# Perpherials.net
KiCad netlist of a schematic drawn in Altium Designer
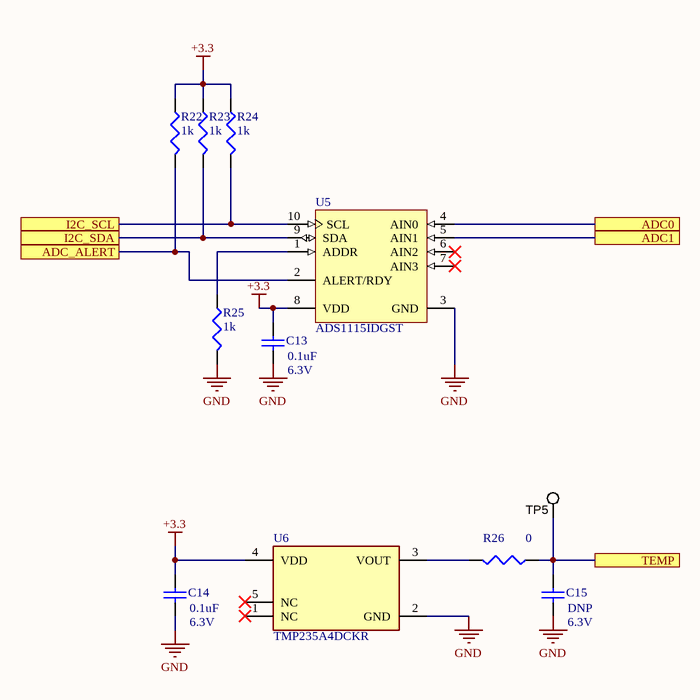
[diagram p0: Perpherials.SchDoc]

(export (version "E")
  (design (tool "Eeschema 10.0.6"))
  (components
    (comp (ref "C13")
      (value "0.1uF")
      (footprint "1608[0603]")
      (description "Capacitor (Semiconductor SIM Model)")
      (fields
        (field (name "VOLTAGE") "6.3V")
        (field (name "MPN") "06036C104KAT4A")
        (field (name "MANUFACTURER") "AVX Corporation")
        (field (name "PUBLISHER") "Altium Limited")
      )
      (libsource (lib "Miscellaneous Devices") (part "Cap Semi"))
    )
    (comp (ref "C14")
      (value "0.1uF")
      (footprint "1608[0603]")
      (description "Capacitor (Semiconductor SIM Model)")
      (fields
        (field (name "VOLTAGE") "6.3V")
        (field (name "MPN") "06036C104KAT4A")
        (field (name "MANUFACTURER") "AVX Corporation")
        (field (name "PUBLISHER") "Altium Limited")
      )
      (libsource (lib "Miscellaneous Devices") (part "Cap Semi"))
    )
    (comp (ref "C15")
      (value "DNP")
      (footprint "1608[0603]")
      (description "Capacitor (Semiconductor SIM Model)")
      (fields
        (field (name "VOLTAGE") "6.3V")
        (field (name "Comment") "Cap Semi")
        (field (name "PUBLISHER") "Altium Limited")
      )
      (libsource (lib "Miscellaneous Devices") (part "Cap Semi"))
    )
    (comp (ref "R22")
      (value "1k")
      (footprint "J1-0603")
      (description "Resistor")
      (fields
        (field (name "MPN") "RC0603FR-071KL")
        (field (name "MANUFACTURER") "Yageo")
        (field (name "PUBLISHER") "Altium Limited")
      )
      (libsource (lib "Miscellaneous Devices") (part "Res3"))
    )
    (comp (ref "R23")
      (value "1k")
      (footprint "J1-0603")
      (description "Resistor")
      (fields
        (field (name "MPN") "RC0603FR-071KL")
        (field (name "MANUFACTURER") "Yageo")
        (field (name "PUBLISHER") "Altium Limited")
      )
      (libsource (lib "Miscellaneous Devices") (part "Res3"))
    )
    (comp (ref "R24")
      (value "1k")
      (footprint "J1-0603")
      (description "Resistor")
      (fields
        (field (name "MPN") "RC0603FR-071KL")
        (field (name "MANUFACTURER") "Yageo")
        (field (name "PUBLISHER") "Altium Limited")
      )
      (libsource (lib "Miscellaneous Devices") (part "Res3"))
    )
    (comp (ref "R25")
      (value "1k")
      (footprint "J1-0603")
      (description "Resistor")
      (fields
        (field (name "MPN") "RC0603FR-071KL")
        (field (name "MANUFACTURER") "Yageo")
        (field (name "PUBLISHER") "Altium Limited")
      )
      (libsource (lib "Miscellaneous Devices") (part "Res3"))
    )
    (comp (ref "R26")
      (value "0")
      (footprint "J1-0603")
      (description "Resistor")
      (fields
        (field (name "MPN") "RC0603JR-070RL")
        (field (name "MANUFACTURER") "Yageo")
        (field (name "PUBLISHER") "Altium Limited")
      )
      (libsource (lib "Miscellaneous Devices") (part "Res3"))
    )
    (comp (ref "TP5")
      (value "5002")
      (footprint "Keystone5002")
      (description "Test Point, Miniature, White, TH")
      (fields (field (name "MANUFACTURER") "Keystone") (field (name "PUBLISHER") "Texas Instruments"))
      (libsource (lib "MDBU017A") (part "5002"))
    )
    (comp (ref "U5")
      (value "ADS1115IDGST")
      (footprint "TI-DGS10_M")
      (fields (field (name "MANUFACTURER") "Texas Instruments") (field (name "MPN") "ADS1115IDGSR"))
      (libsource (lib "Altium Content Vault") (part "TI-ADS1015_1115-10"))
    )
    (comp (ref "U6")
      (value "TMP235A4DCKR")
      (footprint "FP-DCK0005A-MFG")
      (description "SENSOR ANALOG -40C-150C SC70-5")
      (fields
        (field (name "MANUFACTURER") "Texas Instruments")
        (field (name "OCTOPART") "https://octopart.com/tmp235a4dckr-texas+instruments-88184449")
      )
      (libsource (lib "Altium Content Vault") (part "95db8c7ceedc91514cec36ab6d7b9b1"))
    )
  )
  (nets
    (net (code "1") (name "+3.3") (class "Default")
      (node (ref "C13") (pin "2") (pinfunction "2_2") (pintype "passive"))
      (node (ref "C14") (pin "2") (pinfunction "2_2") (pintype "passive"))
      (node (ref "R22") (pin "1") (pinfunction "1_1") (pintype "passive"))
      (node (ref "R23") (pin "1") (pinfunction "1_1") (pintype "passive"))
      (node (ref "R24") (pin "1") (pinfunction "1_1") (pintype "passive"))
      (node (ref "U5") (pin "8") (pinfunction "VDD_8") (pintype "power_in"))
      (node (ref "U6") (pin "4") (pinfunction "VDD_4") (pintype "power_in"))
    )
    (net (code "2") (name "/ADC0") (class "Default")
      (node (ref "U5") (pin "4") (pinfunction "AIN0_4") (pintype "input"))
    )
    (net (code "3") (name "/ADC1") (class "Default")
      (node (ref "U5") (pin "5") (pinfunction "AIN1_5") (pintype "input"))
    )
    (net (code "4") (name "/ADC_ALERT") (class "Default")
      (node (ref "R22") (pin "2") (pinfunction "2_2") (pintype "passive"))
      (node (ref "U5") (pin "2") (pinfunction "ALERT/RDY_2") (pintype "open_collector"))
    )
    (net (code "5") (name "/I2C_SCL") (class "Default")
      (node (ref "R24") (pin "2") (pinfunction "2_2") (pintype "passive"))
      (node (ref "U5") (pin "10") (pinfunction "SCL_10") (pintype "input"))
    )
    (net (code "6") (name "/I2C_SDA") (class "Default")
      (node (ref "R23") (pin "2") (pinfunction "2_2") (pintype "passive"))
      (node (ref "U5") (pin "9") (pinfunction "SDA_9") (pintype "bidirectional"))
    )
    (net (code "7") (name "/TEMP") (class "Default")
      (node (ref "C15") (pin "2") (pinfunction "2_2") (pintype "passive"))
      (node (ref "R26") (pin "1") (pinfunction "1_1") (pintype "passive"))
      (node (ref "TP5") (pin "1") (pintype "passive"))
    )
    (net (code "8") (name "GND") (class "Default")
      (node (ref "C13") (pin "1") (pinfunction "1_1") (pintype "passive"))
      (node (ref "C14") (pin "1") (pinfunction "1_1") (pintype "passive"))
      (node (ref "C15") (pin "1") (pinfunction "1_1") (pintype "passive"))
      (node (ref "R25") (pin "2") (pinfunction "2_2") (pintype "passive"))
      (node (ref "U5") (pin "3") (pinfunction "GND_3") (pintype "power_in"))
      (node (ref "U6") (pin "2") (pinfunction "GND_2") (pintype "power_in"))
    )
    (net (code "9") (name "Net-(U5-ADDR)") (class "Default")
      (node (ref "R25") (pin "1") (pinfunction "1_1") (pintype "passive"))
      (node (ref "U5") (pin "1") (pinfunction "ADDR_1") (pintype "input"))
    )
    (net (code "10") (name "Net-(U6-VOUT)") (class "Default")
      (node (ref "R26") (pin "2") (pinfunction "2_2") (pintype "passive"))
      (node (ref "U6") (pin "3") (pinfunction "VOUT_3") (pintype "passive"))
    )
    (net (code "11") (name "unconnected-(U5-AIN2-Pad6)") (class "Default")
      (node (ref "U5") (pin "6") (pinfunction "AIN2_6") (pintype "input+no_connect"))
    )
    (net (code "12") (name "unconnected-(U5-AIN3-Pad7)") (class "Default")
      (node (ref "U5") (pin "7") (pinfunction "AIN3_7") (pintype "input+no_connect"))
    )
    (net (code "13") (name "unconnected-(U6-NC-Pad1)") (class "Default")
      (node (ref "U6") (pin "1") (pinfunction "NC_1") (pintype "passive+no_connect"))
    )
    (net (code "14") (name "unconnected-(U6-NC-Pad5)") (class "Default")
      (node (ref "U6") (pin "5") (pinfunction "NC_5") (pintype "passive+no_connect"))
    )
  )
)
